# Sheet1.net
KiCad netlist of a schematic drawn in Altium Designer
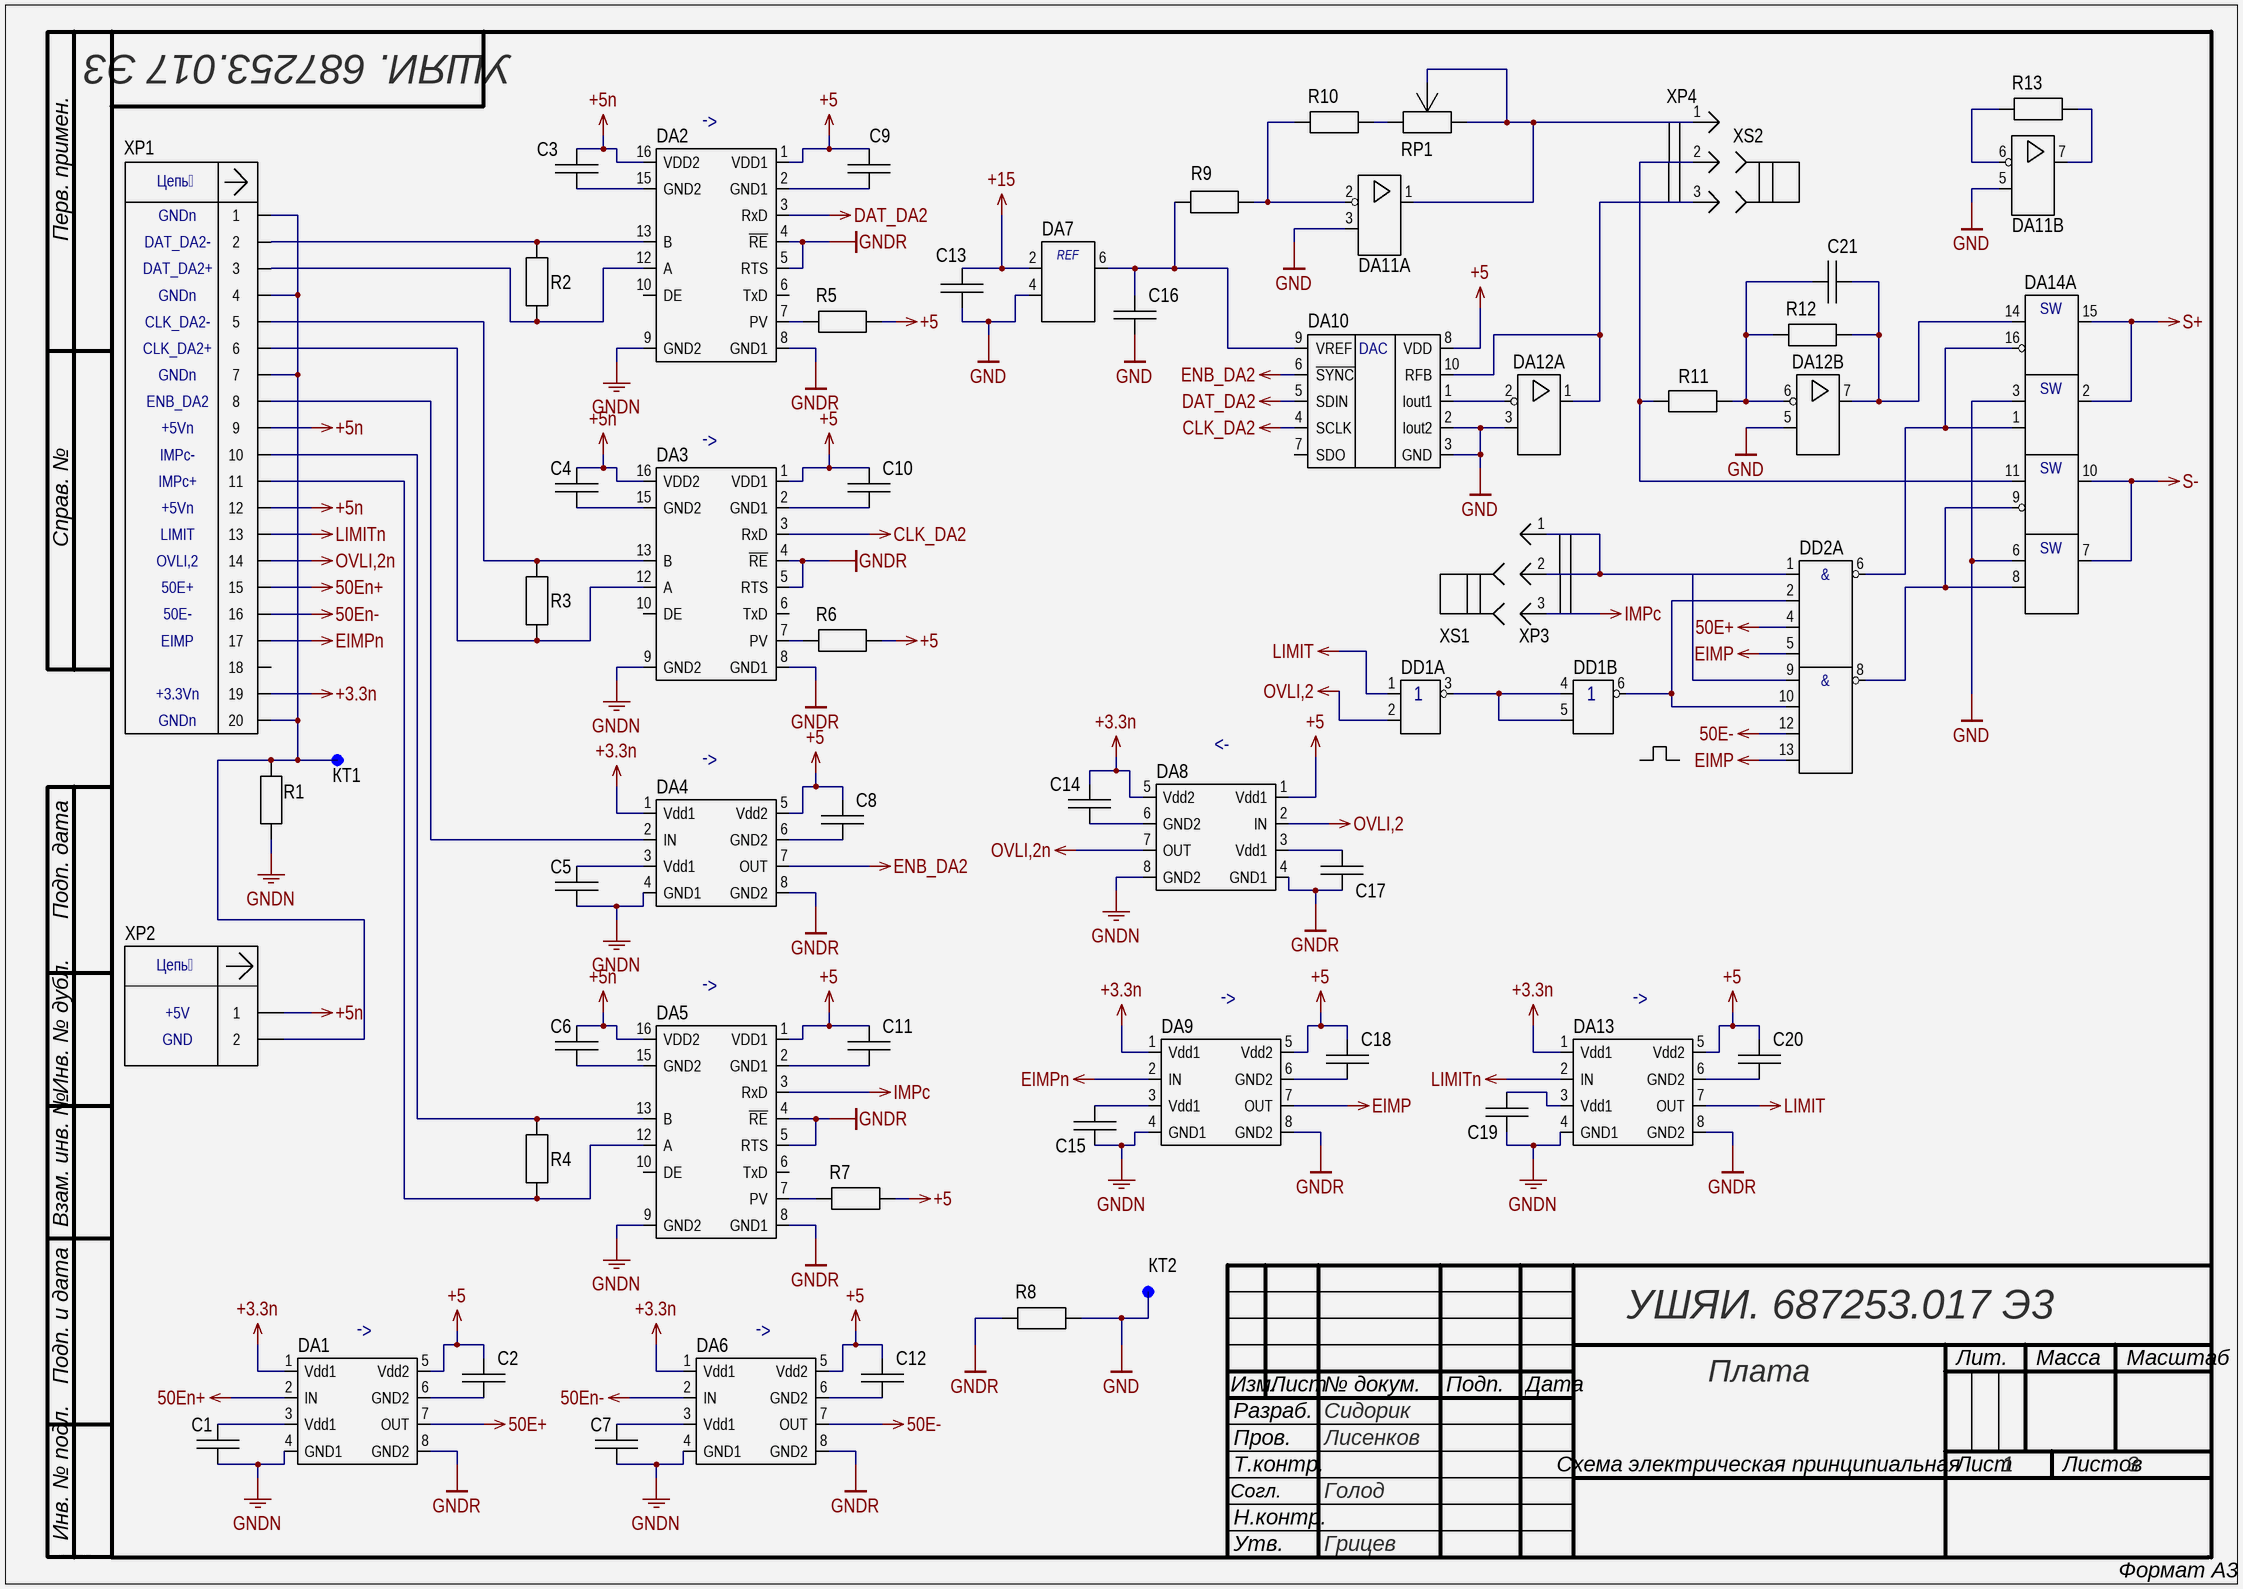
[diagram p0: Sheet1.SchDoc]

(export (version "E")
  (design (tool "Eeschema 10.0.6"))
  (components
    (comp (ref "C1")
      (value "0805-X7R-25 В-0,1 мкФ +-10%")
      (footprint "standard-case:CAP: 0805")
      (libsource (lib "МНИПИ_Конденсаторы") (part "0805-X7R-25 В-0,1 мкФ +-10%"))
    )
    (comp (ref "C2")
      (value "0805-X7R-25 В-0,1 мкФ +-10%")
      (footprint "standard-case:CAP: 0805")
      (libsource (lib "МНИПИ_Конденсаторы") (part "0805-X7R-25 В-0,1 мкФ +-10%"))
    )
    (comp (ref "C3")
      (value "0805-X7R-25 В-0,1 мкФ +-10%")
      (footprint "standard-case:CAP: 0805")
      (libsource (lib "МНИПИ_Конденсаторы") (part "0805-X7R-25 В-0,1 мкФ +-10%"))
    )
    (comp (ref "C4")
      (value "0805-X7R-25 В-0,1 мкФ +-10%")
      (footprint "standard-case:CAP: 0805")
      (libsource (lib "МНИПИ_Конденсаторы") (part "0805-X7R-25 В-0,1 мкФ +-10%"))
    )
    (comp (ref "C5")
      (value "0805-X7R-25 В-0,1 мкФ +-10%")
      (footprint "standard-case:CAP: 0805")
      (libsource (lib "МНИПИ_Конденсаторы") (part "0805-X7R-25 В-0,1 мкФ +-10%"))
    )
    (comp (ref "C6")
      (value "0805-X7R-25 В-0,1 мкФ +-10%")
      (footprint "standard-case:CAP: 0805")
      (libsource (lib "МНИПИ_Конденсаторы") (part "0805-X7R-25 В-0,1 мкФ +-10%"))
    )
    (comp (ref "C7")
      (value "0805-X7R-25 В-0,1 мкФ +-10%")
      (footprint "standard-case:CAP: 0805")
      (libsource (lib "МНИПИ_Конденсаторы") (part "0805-X7R-25 В-0,1 мкФ +-10%"))
    )
    (comp (ref "C8")
      (value "0805-X7R-25 В-0,1 мкФ +-10%")
      (footprint "standard-case:CAP: 0805")
      (libsource (lib "МНИПИ_Конденсаторы") (part "0805-X7R-25 В-0,1 мкФ +-10%"))
    )
    (comp (ref "C9")
      (value "0805-X7R-25 В-0,1 мкФ +-10%")
      (footprint "standard-case:CAP: 0805")
      (libsource (lib "МНИПИ_Конденсаторы") (part "0805-X7R-25 В-0,1 мкФ +-10%"))
    )
    (comp (ref "C10")
      (value "0805-X7R-25 В-0,1 мкФ +-10%")
      (footprint "standard-case:CAP: 0805")
      (libsource (lib "МНИПИ_Конденсаторы") (part "0805-X7R-25 В-0,1 мкФ +-10%"))
    )
    (comp (ref "C11")
      (value "0805-X7R-25 В-0,1 мкФ +-10%")
      (footprint "standard-case:CAP: 0805")
      (libsource (lib "МНИПИ_Конденсаторы") (part "0805-X7R-25 В-0,1 мкФ +-10%"))
    )
    (comp (ref "C12")
      (value "0805-X7R-25 В-0,1 мкФ +-10%")
      (footprint "standard-case:CAP: 0805")
      (libsource (lib "МНИПИ_Конденсаторы") (part "0805-X7R-25 В-0,1 мкФ +-10%"))
    )
    (comp (ref "C13")
      (value "0805-X7R-25 В-0,1 мкФ +-10%")
      (footprint "standard-case:CAP: 0805")
      (libsource (lib "МНИПИ_Конденсаторы") (part "0805-X7R-25 В-0,1 мкФ +-10%"))
    )
    (comp (ref "C14")
      (value "0805-X7R-25 В-0,1 мкФ +-10%")
      (footprint "standard-case:CAP: 0805")
      (libsource (lib "МНИПИ_Конденсаторы") (part "0805-X7R-25 В-0,1 мкФ +-10%"))
    )
    (comp (ref "C15")
      (value "0805-X7R-25 В-0,1 мкФ +-10%")
      (footprint "standard-case:CAP: 0805")
      (libsource (lib "МНИПИ_Конденсаторы") (part "0805-X7R-25 В-0,1 мкФ +-10%"))
    )
    (comp (ref "C16")
      (value "0805-X7R-25 В-0,1 мкФ +-10%")
      (footprint "standard-case:CAP: 0805")
      (libsource (lib "МНИПИ_Конденсаторы") (part "0805-X7R-25 В-0,1 мкФ +-10%"))
    )
    (comp (ref "C17")
      (value "0805-X7R-25 В-0,1 мкФ +-10%")
      (footprint "standard-case:CAP: 0805")
      (libsource (lib "МНИПИ_Конденсаторы") (part "0805-X7R-25 В-0,1 мкФ +-10%"))
    )
    (comp (ref "C18")
      (value "0805-X7R-25 В-0,1 мкФ +-10%")
      (footprint "standard-case:CAP: 0805")
      (libsource (lib "МНИПИ_Конденсаторы") (part "0805-X7R-25 В-0,1 мкФ +-10%"))
    )
    (comp (ref "C19")
      (value "0805-X7R-25 В-0,1 мкФ +-10%")
      (footprint "standard-case:CAP: 0805")
      (libsource (lib "МНИПИ_Конденсаторы") (part "0805-X7R-25 В-0,1 мкФ +-10%"))
    )
    (comp (ref "C20")
      (value "0805-X7R-25 В-0,1 мкФ +-10%")
      (footprint "standard-case:CAP: 0805")
      (libsource (lib "МНИПИ_Конденсаторы") (part "0805-X7R-25 В-0,1 мкФ +-10%"))
    )
    (comp (ref "C21")
      (value "1206-C0G-50 В-22 пФ +-5%")
      (footprint "standard-case:CAP: 1206")
      (libsource (lib "МНИПИ_Конденсаторы") (part "1206-C0G-50 В-22 пФ +-5%"))
    )
    (comp (ref "DA1")
      (value "ADuM1100AR")
      (footprint "standard-case:8-SOIC")
      (libsource (lib "МНИПИ_Микросхемы") (part "ADuM1100AR"))
    )
    (comp (ref "DA2")
      (value "ADM2486BRWZ")
      (footprint "16-SOIC W")
      (description "Isolated RS-485 Transceiver,  20 Mbps data rate, SOIC-16-W")
      (libsource (lib "МНИПИ_Микросхемы") (part "ADM2486BRWZ"))
    )
    (comp (ref "DA3")
      (value "ADM2486BRWZ")
      (footprint "16-SOIC W")
      (description "Isolated RS-485 Transceiver,  20 Mbps data rate, SOIC-16-W")
      (libsource (lib "МНИПИ_Микросхемы") (part "ADM2486BRWZ"))
    )
    (comp (ref "DA4")
      (value "ADuM1100AR")
      (footprint "standard-case:8-SOIC")
      (libsource (lib "МНИПИ_Микросхемы") (part "ADuM1100AR"))
    )
    (comp (ref "DA5")
      (value "ADM2486BRWZ")
      (footprint "16-SOIC W")
      (description "Isolated RS-485 Transceiver,  20 Mbps data rate, SOIC-16-W")
      (libsource (lib "МНИПИ_Микросхемы") (part "ADM2486BRWZ"))
    )
    (comp (ref "DA6")
      (value "ADuM1100AR")
      (footprint "standard-case:8-SOIC")
      (libsource (lib "МНИПИ_Микросхемы") (part "ADuM1100AR"))
    )
    (comp (ref "DA7")
      (value "ADR435BRZ")
      (footprint "standard-case:8-SOIC")
      (libsource (lib "МНИПИ_Микросхемы") (part "ADR435BRZ"))
    )
    (comp (ref "DA8")
      (value "ADuM1100AR")
      (footprint "standard-case:8-SOIC")
      (libsource (lib "") (part "ADuM1100AR_1"))
    )
    (comp (ref "DA9")
      (value "ADuM1100AR")
      (footprint "standard-case:8-SOIC")
      (libsource (lib "МНИПИ_Микросхемы") (part "ADuM1100AR"))
    )
    (comp (ref "DA10")
      (value "AD5443YRM")
      (footprint "10-MSOP")
      (description "12-Bit High Bandwidth\r\nMultiplying DACs with Serial Interface\r10-MSOP")
      (libsource (lib "МНИПИ_Микросхемы") (part "AD5443YRM"))
    )
    (comp (ref "DA11")
      (value "ADA4084-2ARZ")
      (footprint "standard-case:8-SOIC")
      (description "30 V, Low Noise, Rail-to-Rail Input/Output,\r\nLow Power Operational Amplifiers")
      (libsource (lib "МНИПИ_Микросхемы") (part "ADA4084-2ARZ"))
    )
    (comp (ref "DA12")
      (value "ADA4084-2ARZ")
      (footprint "standard-case:8-SOIC")
      (description "30 V, Low Noise, Rail-to-Rail Input/Output,\r\nLow Power Operational Amplifiers")
      (libsource (lib "МНИПИ_Микросхемы") (part "ADA4084-2ARZ"))
    )
    (comp (ref "DA13")
      (value "ADuM1100AR")
      (footprint "standard-case:8-SOIC")
      (libsource (lib "МНИПИ_Микросхемы") (part "ADuM1100AR"))
    )
    (comp (ref "DA14")
      (value "ADG433BR")
      (footprint "standard-case:16-SOIC")
      (description "LC2MOS Precision Quad SPST Switches")
      (libsource (lib "МНИПИ_Микросхемы") (part "ADG433BR_1"))
    )
    (comp (ref "DD1")
      (value "IN74HC00AD")
      (footprint "standard-case:14-soic")
      (description "Quad 2-Input NAND Gate High-Performance Silicon-Gate CMOS.")
      (libsource (lib "МНИПИ_Микросхемы") (part "IN74HC00AD"))
    )
    (comp (ref "DD2")
      (value "IN74HC20D")
      (footprint "standard-case:14-SOIC")
      (description "Dual 4-input  NAND Gate CMOS")
      (libsource (lib "МНИПИ_Микросхемы") (part "IN74HC20D_1"))
    )
    (comp (ref "R1")
      (value "1206-10 Ом+-5%")
      (footprint "МНИПИ_Резисторы:1206")
      (libsource (lib "МНИПИ_Резисторы") (part "1206-10 Ом+-5%"))
    )
    (comp (ref "R2")
      (value "1206-100 Ом+-5%")
      (footprint "МНИПИ_Резисторы:1206")
      (libsource (lib "МНИПИ_Резисторы") (part "1206-100 Ом+-5%"))
    )
    (comp (ref "R3")
      (value "1206-100 Ом+-5%")
      (footprint "МНИПИ_Резисторы:1206")
      (libsource (lib "МНИПИ_Резисторы") (part "1206-100 Ом+-5%"))
    )
    (comp (ref "R4")
      (value "1206-100 Ом+-5%")
      (footprint "МНИПИ_Резисторы:1206")
      (libsource (lib "МНИПИ_Резисторы") (part "1206-100 Ом+-5%"))
    )
    (comp (ref "R5")
      (value "1206-12 кОм+-5%")
      (footprint "МНИПИ_Резисторы:1206")
      (libsource (lib "МНИПИ_Резисторы") (part "1206-12 кОм+-5%"))
    )
    (comp (ref "R6")
      (value "1206-12 кОм+-5%")
      (footprint "МНИПИ_Резисторы:1206")
      (libsource (lib "МНИПИ_Резисторы") (part "1206-12 кОм+-5%"))
    )
    (comp (ref "R7")
      (value "1206-12 кОм+-5%")
      (footprint "МНИПИ_Резисторы:1206")
      (libsource (lib "МНИПИ_Резисторы") (part "1206-12 кОм+-5%"))
    )
    (comp (ref "R8")
      (value "1206-10 Ом+-5%")
      (footprint "МНИПИ_Резисторы:1206")
      (libsource (lib "МНИПИ_Резисторы") (part "1206-10 Ом+-5%"))
    )
    (comp (ref "R9")
      (value "1206-10 кОм+-0,5%")
      (footprint "МНИПИ_Резисторы:1206")
      (libsource (lib "МНИПИ_Резисторы") (part "1206-10 кОм+-0,5%"))
    )
    (comp (ref "R10")
      (value "1206-100 Ом+-0,5%")
      (footprint "МНИПИ_Резисторы:1206")
      (libsource (lib "МНИПИ_Резисторы") (part "1206-100 Ом+-0,5%"))
    )
    (comp (ref "R11")
      (value "1206-10 кОм+-0,5%")
      (footprint "МНИПИ_Резисторы:1206")
      (libsource (lib "МНИПИ_Резисторы") (part "1206-10 кОм+-0,5%"))
    )
    (comp (ref "R12")
      (value "1206-10 кОм+-0,5%")
      (footprint "МНИПИ_Резисторы:1206")
      (libsource (lib "МНИПИ_Резисторы") (part "1206-10 кОм+-0,5%"))
    )
    (comp (ref "R13")
      (value "1206-12 кОм+-1%")
      (footprint "МНИПИ_Резисторы:1206")
      (libsource (lib "МНИПИ_Резисторы") (part "1206-12 кОм+-1%"))
    )
    (comp (ref "RP1")
      (value "3362P-1-103LF")
      (footprint "BOUR-3362P")
      (description "3362 -1/4 ˝ Square Trimpot® Trimming Potentiometer")
      (libsource (lib "МНИПИ_Резисторы") (part "3362P-1-103LF"))
    )
    (comp (ref "XP1")
      (value "BH2-20")
      (footprint "МНИПИ_Разъемы:DS1014-20")
      (description "IDC2-20MS DS1014 20 pin")
      (libsource (lib "МНИПИ_Разъемы") (part "BH2-20"))
    )
    (comp (ref "XP2")
      (value "280370-2")
      (footprint "МНИПИ_Разъемы:280370-2")
      (description "Connector")
      (libsource (lib "МНИПИ_Разъемы") (part "280370-2"))
    )
    (comp (ref "XP3")
      (value "DS1021-1x3")
      (footprint "МНИПИ_Разъемы:3X2.54")
      (description "PLS-3, 2.54 pitch")
      (libsource (lib "МНИПИ_Разъемы") (part "DS1021-1x3_1"))
    )
    (comp (ref "XP4")
      (value "DS1021-1x3")
      (footprint "МНИПИ_Разъемы:3X2.54")
      (description "PLS-3, 2.54 pitch")
      (libsource (lib "МНИПИ_Разъемы") (part "DS1021-1x3_1"))
    )
    (comp (ref "XS1") (value "Jumper, 2.54mm") (libsource (lib "МНИПИ_Разъемы") (part "Jumper, 2.54mm")))
    (comp (ref "XS2") (value "Jumper, 2.54mm") (libsource (lib "МНИПИ_Разъемы") (part "Jumper, 2.54mm")))
    (comp (ref "КТ1")
      (value "Lepestok")
      (footprint "LEPESTOK7750224")
      (libsource (lib "МНИПИ_Разъемы") (part "Lepestok"))
    )
    (comp (ref "КТ2")
      (value "Lepestok")
      (footprint "LEPESTOK7750224")
      (libsource (lib "МНИПИ_Разъемы") (part "Lepestok"))
    )
  )
  (nets
    (net (code "1") (name "+3.3n") (class "Default")
      (node (ref "C14") (pin "1") (pinfunction "1_1") (pintype "passive"))
      (node (ref "DA1") (pin "1") (pinfunction "Vdd1_1") (pintype "passive"))
      (node (ref "DA13") (pin "1") (pinfunction "Vdd1_1") (pintype "passive"))
      (node (ref "DA4") (pin "1") (pinfunction "Vdd1_1") (pintype "passive"))
      (node (ref "DA6") (pin "1") (pinfunction "Vdd1_1") (pintype "passive"))
      (node (ref "DA8") (pin "5") (pinfunction "Vdd2_5") (pintype "passive"))
      (node (ref "DA9") (pin "1") (pinfunction "Vdd1_1") (pintype "passive"))
      (node (ref "XP1") (pin "19") (pinfunction "19_19") (pintype "passive"))
    )
    (net (code "2") (name "+5") (class "Default")
      (node (ref "C10") (pin "2") (pinfunction "2_2") (pintype "passive"))
      (node (ref "C11") (pin "2") (pinfunction "2_2") (pintype "passive"))
      (node (ref "C12") (pin "1") (pinfunction "1_1") (pintype "passive"))
      (node (ref "C18") (pin "1") (pinfunction "1_1") (pintype "passive"))
      (node (ref "C2") (pin "1") (pinfunction "1_1") (pintype "passive"))
      (node (ref "C20") (pin "1") (pinfunction "1_1") (pintype "passive"))
      (node (ref "C8") (pin "1") (pinfunction "1_1") (pintype "passive"))
      (node (ref "C9") (pin "2") (pinfunction "2_2") (pintype "passive"))
      (node (ref "DA1") (pin "5") (pinfunction "Vdd2_5") (pintype "passive"))
      (node (ref "DA10") (pin "8") (pinfunction "VDD_8") (pintype "passive"))
      (node (ref "DA13") (pin "5") (pinfunction "Vdd2_5") (pintype "passive"))
      (node (ref "DA2") (pin "1") (pinfunction "VDD1_1") (pintype "passive"))
      (node (ref "DA3") (pin "1") (pinfunction "VDD1_1") (pintype "passive"))
      (node (ref "DA4") (pin "5") (pinfunction "Vdd2_5") (pintype "passive"))
      (node (ref "DA5") (pin "1") (pinfunction "VDD1_1") (pintype "passive"))
      (node (ref "DA6") (pin "5") (pinfunction "Vdd2_5") (pintype "passive"))
      (node (ref "DA8") (pin "1") (pinfunction "Vdd1_1") (pintype "passive"))
      (node (ref "DA9") (pin "5") (pinfunction "Vdd2_5") (pintype "passive"))
      (node (ref "R5") (pin "1") (pinfunction "1_1") (pintype "passive"))
      (node (ref "R6") (pin "1") (pinfunction "1_1") (pintype "passive"))
      (node (ref "R7") (pin "1") (pinfunction "1_1") (pintype "passive"))
    )
    (net (code "3") (name "+5n") (class "Default")
      (node (ref "C3") (pin "2") (pinfunction "2_2") (pintype "passive"))
      (node (ref "C4") (pin "2") (pinfunction "2_2") (pintype "passive"))
      (node (ref "C6") (pin "2") (pinfunction "2_2") (pintype "passive"))
      (node (ref "DA2") (pin "16") (pinfunction "VDD2_16") (pintype "passive"))
      (node (ref "DA3") (pin "16") (pinfunction "VDD2_16") (pintype "passive"))
      (node (ref "DA5") (pin "16") (pinfunction "VDD2_16") (pintype "passive"))
      (node (ref "XP1") (pin "12") (pinfunction "12_12") (pintype "passive"))
      (node (ref "XP1") (pin "9") (pinfunction "9_9") (pintype "passive"))
      (node (ref "XP2") (pin "1") (pinfunction "1_1") (pintype "passive"))
    )
    (net (code "4") (name "+15") (class "Default")
      (node (ref "C13") (pin "1") (pinfunction "1_1") (pintype "passive"))
      (node (ref "DA7") (pin "2") (pinfunction "VIN_2") (pintype "passive"))
    )
    (net (code "5") (name "50E+") (class "Default")
      (node (ref "DA1") (pin "7") (pinfunction "OUT_7") (pintype "passive"))
      (node (ref "DD2") (pin "4") (pinfunction "C1_4") (pintype "passive"))
    )
    (net (code "6") (name "50E-") (class "Default")
      (node (ref "DA6") (pin "7") (pinfunction "OUT_7") (pintype "passive"))
      (node (ref "DD2") (pin "12") (pinfunction "C2_12") (pintype "passive"))
    )
    (net (code "7") (name "50En+") (class "Default")
      (node (ref "DA1") (pin "2") (pinfunction "IN_2") (pintype "passive"))
      (node (ref "XP1") (pin "15") (pinfunction "15_15") (pintype "passive"))
    )
    (net (code "8") (name "50En-") (class "Default")
      (node (ref "DA6") (pin "2") (pinfunction "IN_2") (pintype "passive"))
      (node (ref "XP1") (pin "16") (pinfunction "16_16") (pintype "passive"))
    )
    (net (code "9") (name "CLK_DA2") (class "Default")
      (node (ref "DA10") (pin "4") (pinfunction "SCLK_4") (pintype "passive"))
      (node (ref "DA3") (pin "3") (pinfunction "RxD_3") (pintype "passive"))
    )
    (net (code "10") (name "DAT_DA2") (class "Default")
      (node (ref "DA10") (pin "5") (pinfunction "SDIN_5") (pintype "passive"))
      (node (ref "DA2") (pin "3") (pinfunction "RxD_3") (pintype "passive"))
    )
    (net (code "11") (name "EIMP") (class "Default")
      (node (ref "DA9") (pin "7") (pinfunction "OUT_7") (pintype "passive"))
      (node (ref "DD2") (pin "13") (pinfunction "D2_13") (pintype "passive"))
      (node (ref "DD2") (pin "5") (pinfunction "D1_5") (pintype "passive"))
    )
    (net (code "12") (name "EIMPn") (class "Default")
      (node (ref "DA9") (pin "2") (pinfunction "IN_2") (pintype "passive"))
      (node (ref "XP1") (pin "17") (pinfunction "17_17") (pintype "passive"))
    )
    (net (code "13") (name "ENB_DA2") (class "Default")
      (node (ref "DA10") (pin "6") (pinfunction "SYNC_6") (pintype "passive"))
      (node (ref "DA4") (pin "7") (pinfunction "OUT_7") (pintype "passive"))
    )
    (net (code "14") (name "GND") (class "Default")
      (node (ref "C13") (pin "2") (pinfunction "2_2") (pintype "passive"))
      (node (ref "C16") (pin "1") (pinfunction "1_1") (pintype "passive"))
      (node (ref "DA10") (pin "2") (pinfunction "Iout2_2") (pintype "passive"))
      (node (ref "DA10") (pin "3") (pinfunction "GND_3") (pintype "passive"))
      (node (ref "DA11") (pin "3") (pinfunction "+IN_A_3") (pintype "passive"))
      (node (ref "DA11") (pin "5") (pinfunction "+IN_B_5") (pintype "passive"))
      (node (ref "DA12") (pin "3") (pinfunction "+IN_A_3") (pintype "passive"))
      (node (ref "DA12") (pin "5") (pinfunction "+IN_B_5") (pintype "passive"))
      (node (ref "DA14") (pin "3") (pinfunction "S1_3") (pintype "passive"))
      (node (ref "DA14") (pin "6") (pinfunction "S4_6") (pintype "passive"))
      (node (ref "DA7") (pin "4") (pinfunction "GND_4") (pintype "passive"))
      (node (ref "R8") (pin "2") (pintype "passive"))
      (node (ref "КТ2") (pin "1") (pinfunction "1_1") (pintype "passive"))
    )
    (net (code "15") (name "GNDN") (class "Default")
      (node (ref "C1") (pin "1") (pinfunction "1_1") (pintype "passive"))
      (node (ref "C15") (pin "1") (pinfunction "1_1") (pintype "passive"))
      (node (ref "C19") (pin "1") (pinfunction "1_1") (pintype "passive"))
      (node (ref "C5") (pin "1") (pinfunction "1_1") (pintype "passive"))
      (node (ref "C7") (pin "1") (pinfunction "1_1") (pintype "passive"))
      (node (ref "DA1") (pin "4") (pinfunction "GND1_4") (pintype "passive"))
      (node (ref "DA13") (pin "4") (pinfunction "GND1_4") (pintype "passive"))
      (node (ref "DA2") (pin "9") (pinfunction "GND2_9") (pintype "passive"))
      (node (ref "DA3") (pin "9") (pinfunction "GND2_9") (pintype "passive"))
      (node (ref "DA4") (pin "4") (pinfunction "GND1_4") (pintype "passive"))
      (node (ref "DA5") (pin "9") (pinfunction "GND2_9") (pintype "passive"))
      (node (ref "DA6") (pin "4") (pinfunction "GND1_4") (pintype "passive"))
      (node (ref "DA8") (pin "8") (pinfunction "GND2_8") (pintype "passive"))
      (node (ref "DA9") (pin "4") (pinfunction "GND1_4") (pintype "passive"))
      (node (ref "R1") (pin "1") (pintype "passive"))
    )
    (net (code "16") (name "GNDR") (class "Default")
      (node (ref "C17") (pin "1") (pinfunction "1_1") (pintype "passive"))
      (node (ref "DA1") (pin "8") (pinfunction "GND2_8") (pintype "passive"))
      (node (ref "DA13") (pin "8") (pinfunction "GND2_8") (pintype "passive"))
      (node (ref "DA2") (pin "4") (pinfunction "RE_4") (pintype "passive"))
      (node (ref "DA2") (pin "5") (pinfunction "RTS_5") (pintype "passive"))
      (node (ref "DA2") (pin "8") (pinfunction "GND1_8") (pintype "passive"))
      (node (ref "DA3") (pin "4") (pinfunction "RE_4") (pintype "passive"))
      (node (ref "DA3") (pin "5") (pinfunction "RTS_5") (pintype "passive"))
      (node (ref "DA3") (pin "8") (pinfunction "GND1_8") (pintype "passive"))
      (node (ref "DA4") (pin "8") (pinfunction "GND2_8") (pintype "passive"))
      (node (ref "DA5") (pin "4") (pinfunction "RE_4") (pintype "passive"))
      (node (ref "DA5") (pin "5") (pinfunction "RTS_5") (pintype "passive"))
      (node (ref "DA5") (pin "8") (pinfunction "GND1_8") (pintype "passive"))
      (node (ref "DA6") (pin "8") (pinfunction "GND2_8") (pintype "passive"))
      (node (ref "DA8") (pin "4") (pinfunction "GND1_4") (pintype "passive"))
      (node (ref "DA9") (pin "8") (pinfunction "GND2_8") (pintype "passive"))
      (node (ref "R8") (pin "1") (pintype "passive"))
    )
    (net (code "17") (name "IMPc") (class "Default")
      (node (ref "DA5") (pin "3") (pinfunction "RxD_3") (pintype "passive"))
      (node (ref "XP3") (pin "3") (pinfunction "3_3") (pintype "passive"))
    )
    (net (code "18") (name "LIMIT") (class "Default")
      (node (ref "DA13") (pin "7") (pinfunction "OUT_7") (pintype "passive"))
      (node (ref "DD1") (pin "1") (pinfunction "A1_1") (pintype "passive"))
    )
    (net (code "19") (name "LIMITn") (class "Default")
      (node (ref "DA13") (pin "2") (pinfunction "IN_2") (pintype "passive"))
      (node (ref "XP1") (pin "13") (pinfunction "13_13") (pintype "passive"))
    )
    (net (code "20") (name "Net-(C1-Pad2)") (class "Default")
      (node (ref "C1") (pin "2") (pinfunction "2_2") (pintype "passive"))
      (node (ref "DA1") (pin "3") (pinfunction "Vdd1_3") (pintype "passive"))
    )
    (net (code "21") (name "Net-(C2-Pad2)") (class "Default")
      (node (ref "C2") (pin "2") (pinfunction "2_2") (pintype "passive"))
      (node (ref "DA1") (pin "6") (pinfunction "GND2_6") (pintype "passive"))
    )
    (net (code "22") (name "Net-(C3-Pad1)") (class "Default")
      (node (ref "C3") (pin "1") (pinfunction "1_1") (pintype "passive"))
      (node (ref "DA2") (pin "15") (pinfunction "GND2_15") (pintype "passive"))
    )
    (net (code "23") (name "Net-(C4-Pad1)") (class "Default")
      (node (ref "C4") (pin "1") (pinfunction "1_1") (pintype "passive"))
      (node (ref "DA3") (pin "15") (pinfunction "GND2_15") (pintype "passive"))
    )
    (net (code "24") (name "Net-(C5-Pad2)") (class "Default")
      (node (ref "C5") (pin "2") (pinfunction "2_2") (pintype "passive"))
      (node (ref "DA4") (pin "3") (pinfunction "Vdd1_3") (pintype "passive"))
    )
    (net (code "25") (name "Net-(C6-Pad1)") (class "Default")
      (node (ref "C6") (pin "1") (pinfunction "1_1") (pintype "passive"))
      (node (ref "DA5") (pin "15") (pinfunction "GND2_15") (pintype "passive"))
    )
    (net (code "26") (name "Net-(C7-Pad2)") (class "Default")
      (node (ref "C7") (pin "2") (pinfunction "2_2") (pintype "passive"))
      (node (ref "DA6") (pin "3") (pinfunction "Vdd1_3") (pintype "passive"))
    )
    (net (code "27") (name "Net-(C8-Pad2)") (class "Default")
      (node (ref "C8") (pin "2") (pinfunction "2_2") (pintype "passive"))
      (node (ref "DA4") (pin "6") (pinfunction "GND2_6") (pintype "passive"))
    )
    (net (code "28") (name "Net-(C9-Pad1)") (class "Default")
      (node (ref "C9") (pin "1") (pinfunction "1_1") (pintype "passive"))
      (node (ref "DA2") (pin "2") (pinfunction "GND1_2") (pintype "passive"))
    )
    (net (code "29") (name "Net-(C10-Pad1)") (class "Default")
      (node (ref "C10") (pin "1") (pinfunction "1_1") (pintype "passive"))
      (node (ref "DA3") (pin "2") (pinfunction "GND1_2") (pintype "passive"))
    )
    (net (code "30") (name "Net-(C11-Pad1)") (class "Default")
      (node (ref "C11") (pin "1") (pinfunction "1_1") (pintype "passive"))
      (node (ref "DA5") (pin "2") (pinfunction "GND1_2") (pintype "passive"))
    )
    (net (code "31") (name "Net-(C12-Pad2)") (class "Default")
      (node (ref "C12") (pin "2") (pinfunction "2_2") (pintype "passive"))
      (node (ref "DA6") (pin "6") (pinfunction "GND2_6") (pintype "passive"))
    )
    (net (code "32") (name "Net-(C14-Pad2)") (class "Default")
      (node (ref "C14") (pin "2") (pinfunction "2_2") (pintype "passive"))
      (node (ref "DA8") (pin "6") (pinfunction "GND2_6") (pintype "passive"))
    )
    (net (code "33") (name "Net-(C15-Pad2)") (class "Default")
      (node (ref "C15") (pin "2") (pinfunction "2_2") (pintype "passive"))
      (node (ref "DA9") (pin "3") (pinfunction "Vdd1_3") (pintype "passive"))
    )
    (net (code "34") (name "Net-(C17-Pad2)") (class "Default")
      (node (ref "C17") (pin "2") (pinfunction "2_2") (pintype "passive"))
      (node (ref "DA8") (pin "3") (pinfunction "Vdd1_3") (pintype "passive"))
    )
    (net (code "35") (name "Net-(C18-Pad2)") (class "Default")
      (node (ref "C18") (pin "2") (pinfunction "2_2") (pintype "passive"))
      (node (ref "DA9") (pin "6") (pinfunction "GND2_6") (pintype "passive"))
    )
    (net (code "36") (name "Net-(C19-Pad2)") (class "Default")
      (node (ref "C19") (pin "2") (pinfunction "2_2") (pintype "passive"))
      (node (ref "DA13") (pin "3") (pinfunction "Vdd1_3") (pintype "passive"))
    )
    (net (code "37") (name "Net-(C20-Pad2)") (class "Default")
      (node (ref "C20") (pin "2") (pinfunction "2_2") (pintype "passive"))
      (node (ref "DA13") (pin "6") (pinfunction "GND2_6") (pintype "passive"))
    )
    (net (code "38") (name "Net-(DA2-A)") (class "Default")
      (node (ref "DA2") (pin "12") (pinfunction "A_12") (pintype "passive"))
      (node (ref "R2") (pin "1") (pinfunction "1_1") (pintype "passive"))
      (node (ref "XP1") (pin "3") (pinfunction "3_3") (pintype "passive"))
    )
    (net (code "39") (name "Net-(DA2-B)") (class "Default")
      (node (ref "DA2") (pin "13") (pinfunction "B_13") (pintype "passive"))
      (node (ref "R2") (pin "2") (pinfunction "1_2") (pintype "passive"))
      (node (ref "XP1") (pin "2") (pinfunction "2_2") (pintype "passive"))
    )
    (net (code "40") (name "Net-(DA2-PV)") (class "Default")
      (node (ref "DA2") (pin "7") (pinfunction "PV_7") (pintype "passive"))
      (node (ref "R5") (pin "2") (pinfunction "2_2") (pintype "passive"))
    )
    (net (code "41") (name "Net-(DA3-A)") (class "Default")
      (node (ref "DA3") (pin "12") (pinfunction "A_12") (pintype "passive"))
      (node (ref "R3") (pin "1") (pinfunction "1_1") (pintype "passive"))
      (node (ref "XP1") (pin "6") (pinfunction "6_6") (pintype "passive"))
    )
    (net (code "42") (name "Net-(DA3-B)") (class "Default")
      (node (ref "DA3") (pin "13") (pinfunction "B_13") (pintype "passive"))
      (node (ref "R3") (pin "2") (pinfunction "1_2") (pintype "passive"))
      (node (ref "XP1") (pin "5") (pinfunction "5_5") (pintype "passive"))
    )
    (net (code "43") (name "Net-(DA3-PV)") (class "Default")
      (node (ref "DA3") (pin "7") (pinfunction "PV_7") (pintype "passive"))
      (node (ref "R6") (pin "2") (pinfunction "2_2") (pintype "passive"))
    )
    (net (code "44") (name "Net-(DA4-IN)") (class "Default")
      (node (ref "DA4") (pin "2") (pinfunction "IN_2") (pintype "passive"))
      (node (ref "XP1") (pin "8") (pinfunction "8_8") (pintype "passive"))
    )
    (net (code "45") (name "Net-(DA5-A)") (class "Default")
      (node (ref "DA5") (pin "12") (pinfunction "A_12") (pintype "passive"))
      (node (ref "R4") (pin "1") (pinfunction "1_1") (pintype "passive"))
      (node (ref "XP1") (pin "11") (pinfunction "11_11") (pintype "passive"))
    )
    (net (code "46") (name "Net-(DA5-B)") (class "Default")
      (node (ref "DA5") (pin "13") (pinfunction "B_13") (pintype "passive"))
      (node (ref "R4") (pin "2") (pinfunction "1_2") (pintype "passive"))
      (node (ref "XP1") (pin "10") (pinfunction "10_10") (pintype "passive"))
    )
    (net (code "47") (name "Net-(DA5-PV)") (class "Default")
      (node (ref "DA5") (pin "7") (pinfunction "PV_7") (pintype "passive"))
      (node (ref "R7") (pin "2") (pinfunction "2_2") (pintype "passive"))
    )
    (net (code "48") (name "Net-(DA10-Iout1)") (class "Default")
      (node (ref "DA10") (pin "1") (pinfunction "Iout1_1") (pintype "passive"))
      (node (ref "DA12") (pin "2") (pinfunction "-IN_A_2") (pintype "passive"))
    )
    (net (code "49") (name "Net-(DA10-RFB)") (class "Default")
      (node (ref "DA10") (pin "10") (pinfunction "RFB_10") (pintype "passive"))
      (node (ref "DA12") (pin "1") (pinfunction "OUT_A_1") (pintype "passive"))
      (node (ref "XP4") (pin "3") (pinfunction "3_3") (pintype "passive"))
    )
    (net (code "50") (name "Net-(DA10-VREF)") (class "Default")
      (node (ref "C16") (pin "2") (pinfunction "2_2") (pintype "passive"))
      (node (ref "DA10") (pin "9") (pinfunction "VREF_9") (pintype "passive"))
      (node (ref "DA7") (pin "6") (pinfunction "VOUT_6") (pintype "passive"))
      (node (ref "R9") (pin "1") (pinfunction "1_1") (pintype "passive"))
    )
    (net (code "51") (name "Net-(DA11A--IN_A)") (class "Default")
      (node (ref "DA11") (pin "2") (pinfunction "-IN_A_2") (pintype "passive"))
      (node (ref "R10") (pin "1") (pinfunction "1_1") (pintype "passive"))
      (node (ref "R9") (pin "2") (pinfunction "2_2") (pintype "passive"))
    )
    (net (code "52") (name "Net-(DA11A-OUT_A)") (class "Default")
      (node (ref "DA11") (pin "1") (pinfunction "OUT_A_1") (pintype "passive"))
      (node (ref "RP1") (pin "1") (pintype "passive"))
      (node (ref "RP1") (pin "2") (pinfunction "WIPER_2") (pintype "passive"))
      (node (ref "XP4") (pin "1") (pinfunction "1_1") (pintype "passive"))
    )
    (net (code "53") (name "Net-(DA11B--IN_B)") (class "Default")
      (node (ref "DA11") (pin "6") (pinfunction "-IN_B_6") (pintype "passive"))
      (node (ref "R13") (pin "1") (pinfunction "1_1") (pintype "passive"))
    )
    (net (code "54") (name "Net-(DA11B-OUT_B)") (class "Default")
      (node (ref "DA11") (pin "7") (pinfunction "OUT_B_7") (pintype "passive"))
      (node (ref "R13") (pin "2") (pinfunction "2_2") (pintype "passive"))
    )
    (net (code "55") (name "Net-(DA12B--IN_B)") (class "Default")
      (node (ref "C21") (pin "1") (pinfunction "1_1") (pintype "passive"))
      (node (ref "DA12") (pin "6") (pinfunction "-IN_B_6") (pintype "passive"))
      (node (ref "R11") (pin "2") (pinfunction "2_2") (pintype "passive"))
      (node (ref "R12") (pin "1") (pinfunction "1_1") (pintype "passive"))
    )
    (net (code "56") (name "Net-(DA12B-OUT_B)") (class "Default")
      (node (ref "C21") (pin "2") (pinfunction "2_2") (pintype "passive"))
      (node (ref "DA12") (pin "7") (pinfunction "OUT_B_7") (pintype "passive"))
      (node (ref "DA14") (pin "14") (pinfunction "S2_14") (pintype "passive"))
      (node (ref "R12") (pin "2") (pinfunction "2_2") (pintype "passive"))
    )
    (net (code "57") (name "Net-(DA14A-IN1)") (class "Default")
      (node (ref "DA14") (pin "1") (pinfunction "IN1_1") (pintype "passive"))
      (node (ref "DA14") (pin "16") (pinfunction "IN2_16") (pintype "passive"))
      (node (ref "DD2") (pin "6") (pinfunction "Y1_6") (pintype "passive"))
    )
    (net (code "58") (name "Net-(DA14A-IN3)") (class "Default")
      (node (ref "DA14") (pin "8") (pinfunction "IN4_8") (pintype "passive"))
      (node (ref "DA14") (pin "9") (pinfunction "IN3_9") (pintype "passive"))
      (node (ref "DD2") (pin "8") (pinfunction "Y2_8") (pintype "passive"))
    )
    (net (code "59") (name "Net-(DA14A-S3)") (class "Default")
      (node (ref "DA14") (pin "11") (pinfunction "S3_11") (pintype "passive"))
      (node (ref "R11") (pin "1") (pinfunction "1_1") (pintype "passive"))
      (node (ref "XP4") (pin "2") (pinfunction "2_2") (pintype "passive"))
    )
    (net (code "60") (name "Net-(DD1A-Y1)") (class "Default")
      (node (ref "DD1") (pin "3") (pinfunction "Y1_3") (pintype "passive"))
      (node (ref "DD1") (pin "4") (pinfunction "A2_4") (pintype "passive"))
      (node (ref "DD1") (pin "5") (pinfunction "B2_5") (pintype "passive"))
    )
    (net (code "61") (name "Net-(DD1B-Y2)") (class "Default")
      (node (ref "DD1") (pin "6") (pinfunction "Y2_6") (pintype "passive"))
      (node (ref "DD2") (pin "10") (pinfunction "B2_10") (pintype "passive"))
      (node (ref "DD2") (pin "2") (pinfunction "B1_2") (pintype "passive"))
    )
    (net (code "62") (name "Net-(DD2A-A1)") (class "Default")
      (node (ref "DD2") (pin "1") (pinfunction "A1_1") (pintype "passive"))
      (node (ref "DD2") (pin "9") (pinfunction "A2_9") (pintype "passive"))
      (node (ref "XP3") (pin "1") (pinfunction "1_1") (pintype "passive"))
      (node (ref "XP3") (pin "2") (pinfunction "2_2") (pintype "passive"))
    )
    (net (code "63") (name "Net-(R1-Pad2)") (class "Default")
      (node (ref "R1") (pin "2") (pintype "passive"))
      (node (ref "XP1") (pin "1") (pinfunction "1_1") (pintype "passive"))
      (node (ref "XP1") (pin "20") (pinfunction "20_20") (pintype "passive"))
      (node (ref "XP1") (pin "4") (pinfunction "4_4") (pintype "passive"))
      (node (ref "XP1") (pin "7") (pinfunction "7_7") (pintype "passive"))
      (node (ref "XP2") (pin "2") (pinfunction "2_2") (pintype "passive"))
      (node (ref "КТ1") (pin "1") (pinfunction "1_1") (pintype "passive"))
    )
    (net (code "64") (name "Net-(R10-1-Pad2)") (class "Default")
      (node (ref "R10") (pin "2") (pinfunction "1_2") (pintype "passive"))
      (node (ref "RP1") (pin "3") (pintype "passive"))
    )
    (net (code "65") (name "OVLI,2") (class "Default")
      (node (ref "DA8") (pin "2") (pinfunction "IN_2") (pintype "passive"))
      (node (ref "DD1") (pin "2") (pinfunction "B1_2") (pintype "passive"))
    )
    (net (code "66") (name "OVLI,2n") (class "Default")
      (node (ref "DA8") (pin "7") (pinfunction "OUT_7") (pintype "passive"))
      (node (ref "XP1") (pin "14") (pinfunction "14_14") (pintype "passive"))
    )
    (net (code "67") (name "S+") (class "Default")
      (node (ref "DA14") (pin "15") (pinfunction "D2_15") (pintype "passive"))
      (node (ref "DA14") (pin "2") (pinfunction "D1_2") (pintype "passive"))
    )
    (net (code "68") (name "S-") (class "Default")
      (node (ref "DA14") (pin "10") (pinfunction "D3_10") (pintype "passive"))
      (node (ref "DA14") (pin "7") (pinfunction "D4_7") (pintype "passive"))
    )
    (net (code "69") (name "unconnected-(DA2-DE-Pad10)") (class "Default")
      (node (ref "DA2") (pin "10") (pinfunction "DE_10") (pintype "passive"))
    )
    (net (code "70") (name "unconnected-(DA2-TxD-Pad6)") (class "Default")
      (node (ref "DA2") (pin "6") (pinfunction "TxD_6") (pintype "passive"))
    )
    (net (code "71") (name "unconnected-(DA3-DE-Pad10)") (class "Default")
      (node (ref "DA3") (pin "10") (pinfunction "DE_10") (pintype "passive"))
    )
    (net (code "72") (name "unconnected-(DA3-TxD-Pad6)") (class "Default")
      (node (ref "DA3") (pin "6") (pinfunction "TxD_6") (pintype "passive"))
    )
    (net (code "73") (name "unconnected-(DA5-DE-Pad10)") (class "Default")
      (node (ref "DA5") (pin "10") (pinfunction "DE_10") (pintype "passive"))
    )
    (net (code "74") (name "unconnected-(DA5-TxD-Pad6)") (class "Default")
      (node (ref "DA5") (pin "6") (pinfunction "TxD_6") (pintype "passive"))
    )
    (net (code "75") (name "unconnected-(DA10-SDO-Pad7)") (class "Default")
      (node (ref "DA10") (pin "7") (pinfunction "SDO_7") (pintype "passive"))
    )
    (net (code "76") (name "unconnected-(XP1-Pad18)") (class "Default")
      (node (ref "XP1") (pin "18") (pinfunction "18_18") (pintype "passive"))
    )
  )
)
